# Gas_Sampler-Flow_Sensor.net
KiCad netlist of a schematic drawn in Altium Designer
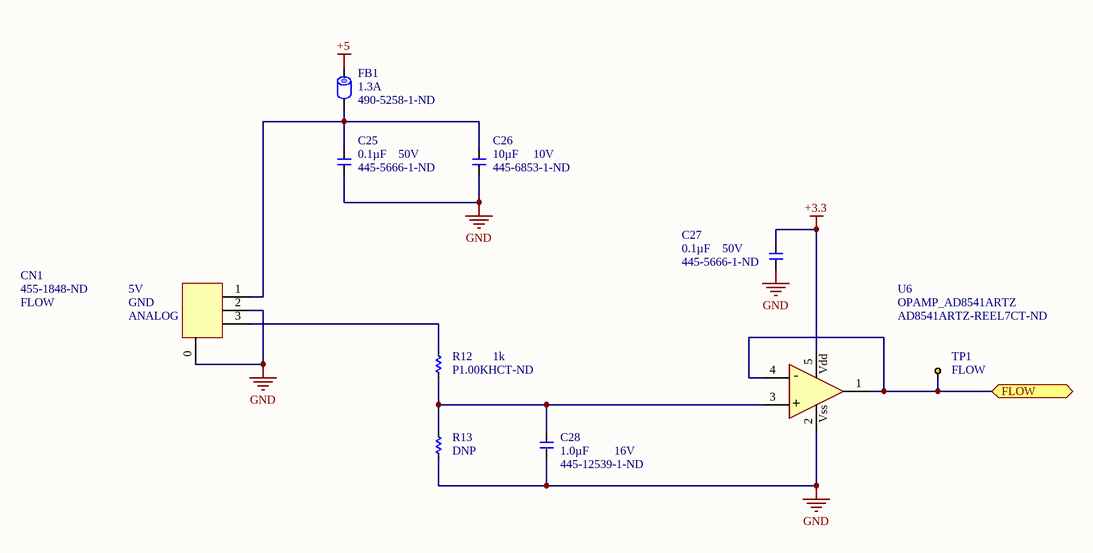
[diagram p0: Gas_Sampler-Flow_Sensor.SchDoc]

(export (version "E")
  (design (tool "Eeschema 10.0.6"))
  (components
    (comp (ref "C25")
      (value "0.1µF")
      (footprint "C0603")
      (description "CAP CER 0.1UF 50V 10% X7R 0603")
      (fields
        (field (name "MANUFACTURER") "TDK Corporation")
        (field (name "MANUFACTURER PART NUMBER") "CGA3E2X7R1H104K080AA")
        (field (name "VOLTAGE - RATED") "50V")
        (field (name "SUPPLIER PART NUMBER 1") "445-5666-1-ND")
      )
      (libsource (lib "capacitor") (part "CAP_CER_0603_0.1UF_50V_10%_X7R"))
    )
    (comp (ref "C26")
      (value "10µF")
      (footprint "C0603")
      (description "CAP CER 10UF 10V X5R 0603")
      (fields
        (field (name "MANUFACTURER") "TDK Corporation")
        (field (name "MANUFACTURER PART NUMBER") "C1608X5R1A106M080AC")
        (field (name "VOLTAGE - RATED") "10V")
        (field (name "SUPPLIER PART NUMBER 1") "445-6853-1-ND")
      )
      (libsource (lib "capacitor") (part "CAP_CER_0603_10UF_10V_20%_X5R"))
    )
    (comp (ref "C27")
      (value "0.1µF")
      (footprint "C0603")
      (description "CAP CER 0.1UF 50V 10% X7R 0603")
      (fields
        (field (name "MANUFACTURER") "TDK Corporation")
        (field (name "MANUFACTURER PART NUMBER") "CGA3E2X7R1H104K080AA")
        (field (name "VOLTAGE - RATED") "50V")
        (field (name "SUPPLIER PART NUMBER 1") "445-5666-1-ND")
      )
      (libsource (lib "capacitor") (part "CAP_CER_0603_0.1UF_50V_10%_X7R"))
    )
    (comp (ref "C28")
      (value "1.0µF")
      (footprint "C0603")
      (description "CAP CER 1UF 16V 10% X7R 0603")
      (fields
        (field (name "MANUFACTURER") "TDK Corporation")
        (field (name "MANUFACTURER PART NUMBER") "CGA3E1X7R1C105K080AC")
        (field (name "SUPPLIER PART NUMBER 1") "445-12539-1-ND")
        (field (name "VOLTAGE - RATED") "16V")
      )
      (libsource (lib "capacitor") (part "CAP_CER_0603_1UF_16V_10%_X7R"))
    )
    (comp (ref "CN1")
      (value "FLOW")
      (footprint "JST_PA_S03B-PASK-2")
      (description "CONN HEADER PA 3POS SIDE 2MM TIN")
      (fields
        (field (name "MANUFACTURER") "JST Sales America Inc.")
        (field (name "MANUFACTURER PART NUMBER") "S03B-PASK-2(LF)(SN)")
        (field (name "SUPPLIER PART NUMBER 1") "455-1848-ND")
      )
      (libsource (lib "jst pa") (part "JST_PA_RA_TH_GUIDE_3POS"))
    )
    (comp (ref "FB1")
      (value "FERRITE_BEAD_0603_1.3A_600_OHM")
      (footprint "R0603")
      (description "FERRITE BEAD 600 OHM 0603 1LN")
      (fields
        (field (name "MANUFACTURER") "Murata Electronics North America")
        (field (name "MANUFACTURER PART NUMBER") "BLM18KG601SN1D")
        (field (name "CURRENT RATING (MAX)") "1.3A")
        (field (name "SUPPLIER PART NUMBER 1") "490-5258-1-ND")
      )
      (libsource (lib "miscellaneous") (part "FERRITE_BEAD_0603_1.3A_600_OHM"))
    )
    (comp (ref "R12")
      (value "1k")
      (footprint "R0603")
      (description "RES 1K OHM 1/10W 1% 0603 SMD")
      (fields
        (field (name "MANUFACTURER") "Panasonic Electronic Components")
        (field (name "MANUFACTURER PART NUMBER") "ERJ-3EKF1001V")
        (field (name "SUPPLIER PART NUMBER 1") "P1.00KHCT-ND")
      )
      (libsource (lib "resistor") (part "RES_0603_1K_OHM_1/10W_1%"))
    )
    (comp (ref "R13")
      (value "DNP")
      (footprint "R0603")
      (description "RES DNP 0603 SMD")
      (fields (field (name "PART NUMBER") "000-00000-00") (field (name "Comment") "RES_0603_DNP"))
      (libsource (lib "resistor") (part "RES_0603_DNP"))
    )
    (comp (ref "TP1")
      (value "FLOW")
      (footprint "TP_KEYSTONE_5001")
      (description "PC TEST POINT TH RING")
      (fields
        (field (name "MANUFACTURER") "Keystone Electronics")
        (field (name "MANUFACTURER PART NUMBER") "5001")
      )
      (libsource (lib "miscellaneous") (part "TEST_KEYSTONE5001"))
    )
    (comp (ref "U6")
      (value "OPAMP_AD8541ARTZ")
      (footprint "5SOT23")
      (description "IC OPAMP GP R-R CMOS SOT23-5")
      (fields
        (field (name "MANUFACTURER") "Analog Devices Inc")
        (field (name "MANUFACTURER PART NUMBER") "AD8541ARTZ-REEL7")
        (field (name "SUPPLIER PART NUMBER 1") "AD8541ARTZ-REEL7CT-ND")
      )
      (libsource (lib "ic_analog") (part "OPAMP_AD8541ARTZ"))
    )
  )
  (nets
    (net (code "1") (name "+3.3") (class "Default")
      (node (ref "C27") (pin "1") (pintype "passive"))
      (node (ref "U6") (pin "5") (pinfunction "VDD_5") (pintype "passive"))
    )
    (net (code "2") (name "+5") (class "Default")
      (node (ref "FB1") (pin "1") (pinfunction "1_1") (pintype "passive"))
    )
    (net (code "3") (name "/FLOW") (class "Default")
      (node (ref "TP1") (pin "1") (pintype "passive"))
      (node (ref "U6") (pin "1") (pinfunction "OUT_1") (pintype "passive"))
      (node (ref "U6") (pin "4") (pinfunction "IN-_4") (pintype "passive"))
    )
    (net (code "4") (name "GND") (class "Default")
      (node (ref "C25") (pin "2") (pintype "passive"))
      (node (ref "C26") (pin "2") (pintype "passive"))
      (node (ref "C27") (pin "2") (pintype "passive"))
      (node (ref "C28") (pin "2") (pintype "passive"))
      (node (ref "CN1") (pin "0") (pinfunction "CHAS_0") (pintype "passive"))
      (node (ref "CN1") (pin "2") (pinfunction "2_2") (pintype "passive"))
      (node (ref "R13") (pin "1") (pintype "passive"))
      (node (ref "U6") (pin "2") (pinfunction "VSS_2") (pintype "passive"))
    )
    (net (code "5") (name "Net-(C25-Pad1)") (class "Default")
      (node (ref "C25") (pin "1") (pintype "passive"))
      (node (ref "C26") (pin "1") (pintype "passive"))
      (node (ref "CN1") (pin "1") (pinfunction "1_1") (pintype "passive"))
      (node (ref "FB1") (pin "2") (pinfunction "2_2") (pintype "passive"))
    )
    (net (code "6") (name "Net-(CN1-Pad3)") (class "Default")
      (node (ref "CN1") (pin "3") (pinfunction "3_3") (pintype "passive"))
      (node (ref "R12") (pin "2") (pintype "passive"))
    )
    (net (code "7") (name "Net-(U6-IN+)") (class "Default")
      (node (ref "C28") (pin "1") (pintype "passive"))
      (node (ref "R12") (pin "1") (pintype "passive"))
      (node (ref "R13") (pin "2") (pintype "passive"))
      (node (ref "U6") (pin "3") (pinfunction "IN+_3") (pintype "passive"))
    )
  )
)
